# IgnitionSchem.net
KiCad netlist of a schematic drawn in Altium Designer
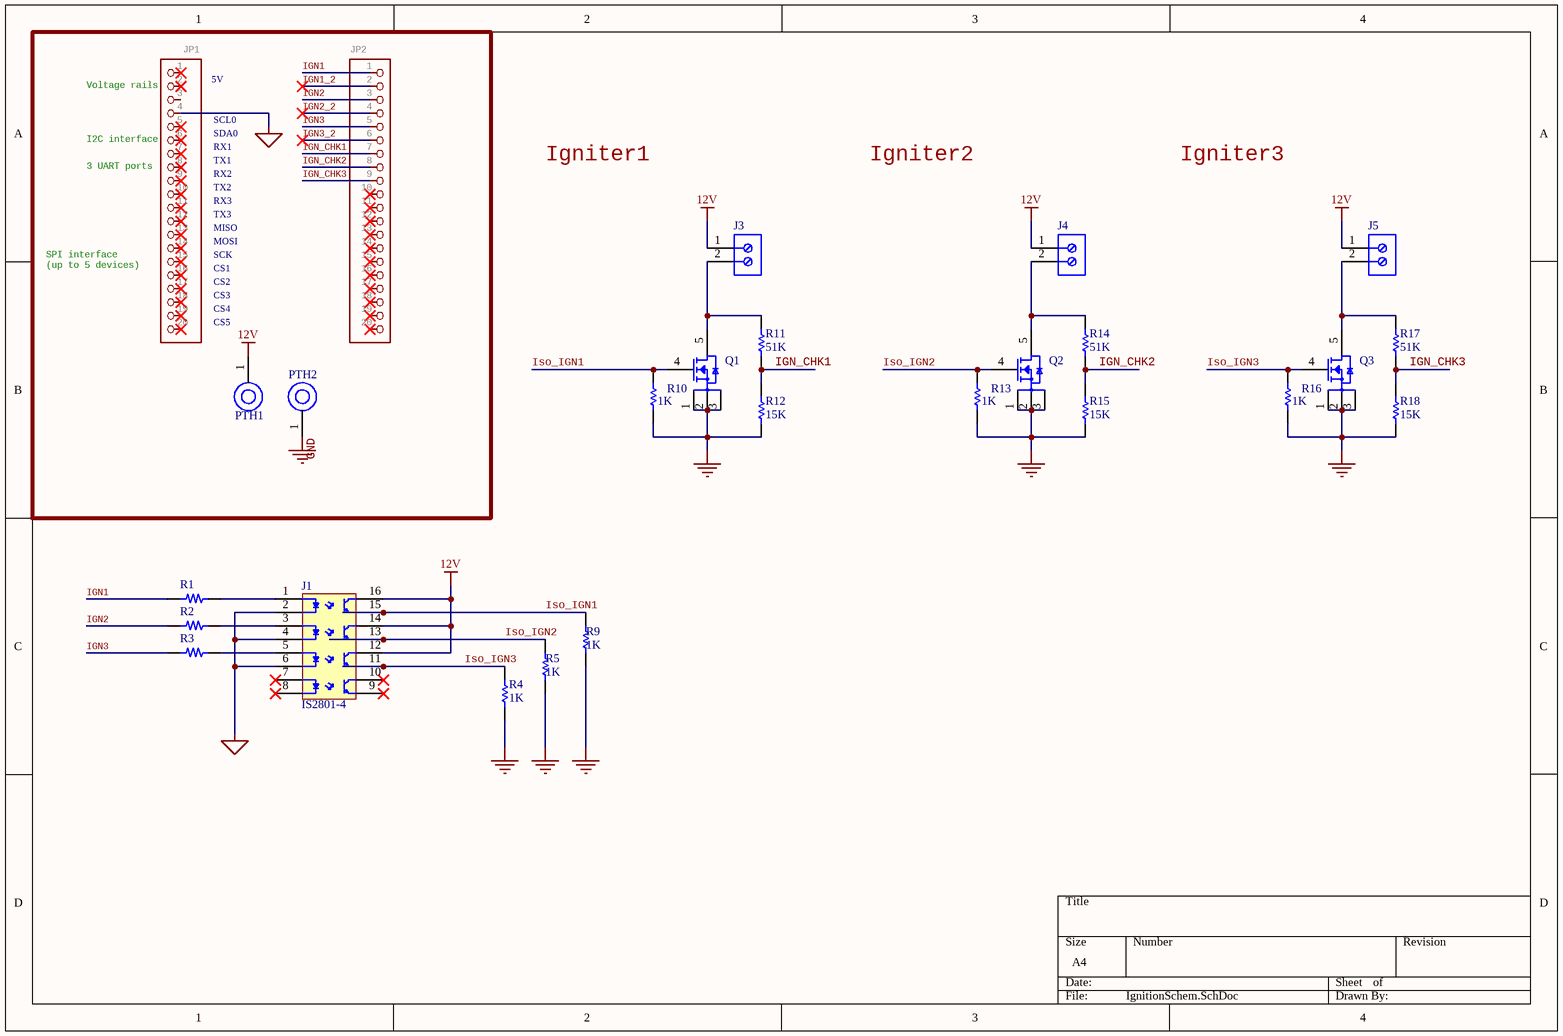
[diagram p0: IgnitionSchem.SchDoc]

(export (version "E")
  (design (tool "Eeschema 10.0.6"))
  (components
    (comp (ref "J1")
      (value "IS2801-4")
      (footprint "SOP127P680X220-16N")
      (description "Optocoupler DC-IN 4-CH Transistor DC-OUT 16-Pin T/R")
      (fields (field (name "MANUFACTURER") "Isocom"))
      (libsource (lib "Avionics_lib") (part "IS2801-4"))
    )
    (comp (ref "J3")
      (value "1725656")
      (footprint "PHOE-1725656-2")
      (description "Male Header, Pitch 2.54 mm, 1 x 2 Position, Height 9 mm, Tail Length 3.5 mm")
      (fields (field (name "MANUFACTURER") "Phoenix Contact"))
      (libsource (lib "Altium Content Vault") (part "CN-1P-F-TB2"))
    )
    (comp (ref "J4")
      (value "1725656")
      (footprint "PHOE-1725656-2")
      (description "Male Header, Pitch 2.54 mm, 1 x 2 Position, Height 9 mm, Tail Length 3.5 mm")
      (fields (field (name "MANUFACTURER") "Phoenix Contact"))
      (libsource (lib "Altium Content Vault") (part "CN-1P-F-TB2"))
    )
    (comp (ref "J5")
      (value "1725656")
      (footprint "PHOE-1725656-2")
      (description "Male Header, Pitch 2.54 mm, 1 x 2 Position, Height 9 mm, Tail Length 3.5 mm")
      (fields (field (name "MANUFACTURER") "Phoenix Contact"))
      (libsource (lib "Altium Content Vault") (part "CN-1P-F-TB2"))
    )
    (comp (ref "JP1")
      (value "PINHD-1X20")
      (footprint "1X20")
      (description "PIN HEADER")
      (libsource (lib "adafruit") (part "PINHD-1X20"))
    )
    (comp (ref "JP2")
      (value "PINHD-1X20")
      (footprint "1X20")
      (description "PIN HEADER")
      (libsource (lib "adafruit") (part "PINHD-1X20"))
    )
    (comp (ref "PTH1")
      (value "WIRE_CONNECTOR")
      (footprint "Wire Mount")
      (libsource (lib "Avionics_lib") (part "WIRE_CONNECTOR"))
    )
    (comp (ref "PTH2")
      (value "WIRE_CONNECTOR")
      (footprint "Wire Mount")
      (libsource (lib "Avionics_lib") (part "WIRE_CONNECTOR"))
    )
    (comp (ref "Q1")
      (value "Ingiter FET")
      (footprint "PSMN5R6-60YLX")
      (description "PSMN5R6-60YL - N-channel 60 V, 5.6 mO logic level MOSFET in LFPAK56")
      (fields
        (field (name "MANUFACTURER") "Nexperia")
        (field (name "MANUFACTURER PART NUMBER") "PSMN5R6-60YLX")
      )
      (libsource (lib "Avionics_lib") (part "PSMN5R6-60YLX"))
    )
    (comp (ref "Q2")
      (value "Ingiter FET")
      (footprint "PSMN5R6-60YLX")
      (description "PSMN5R6-60YL - N-channel 60 V, 5.6 mO logic level MOSFET in LFPAK56")
      (fields
        (field (name "MANUFACTURER") "Nexperia")
        (field (name "MANUFACTURER PART NUMBER") "PSMN5R6-60YLX")
      )
      (libsource (lib "Avionics_lib") (part "PSMN5R6-60YLX"))
    )
    (comp (ref "Q3")
      (value "Ingiter FET")
      (footprint "PSMN5R6-60YLX")
      (description "PSMN5R6-60YL - N-channel 60 V, 5.6 mO logic level MOSFET in LFPAK56")
      (fields
        (field (name "MANUFACTURER") "Nexperia")
        (field (name "MANUFACTURER PART NUMBER") "PSMN5R6-60YLX")
      )
      (libsource (lib "Avionics_lib") (part "PSMN5R6-60YLX"))
    )
    (comp (ref "R1")
      (value "WR06X331JTL")
      (footprint "WR06X331")
      (description "Res Thick Film 0603 330 Ohm 5% 0.1W(1/10W) ±100ppm/C SMD T/R")
      (fields (field (name "MANUFACTURER") "Walsin Technologies") (field (name "TOLERANCE") "5%"))
      (libsource (lib "Avionics_lib") (part "WR06X331JTL"))
    )
    (comp (ref "R2")
      (value "WR06X331JTL")
      (footprint "WR06X331")
      (description "Res Thick Film 0603 330 Ohm 5% 0.1W(1/10W) ±100ppm/C SMD T/R")
      (fields (field (name "MANUFACTURER") "Walsin Technologies") (field (name "TOLERANCE") "5%"))
      (libsource (lib "Avionics_lib") (part "WR06X331JTL"))
    )
    (comp (ref "R3")
      (value "WR06X331JTL")
      (footprint "WR06X331")
      (description "Res Thick Film 0603 330 Ohm 5% 0.1W(1/10W) ±100ppm/C SMD T/R")
      (fields (field (name "MANUFACTURER") "Walsin Technologies") (field (name "TOLERANCE") "5%"))
      (libsource (lib "Avionics_lib") (part "WR06X331JTL"))
    )
    (comp (ref "R4")
      (value "1K")
      (footprint "RESC2013X50X30NL20T20")
      (fields (field (name "PART NUMBER") "CRCW08051K00FKEA") (field (name "MANUFACTURER") "Vishay Dale"))
      (libsource (lib "Altium Content Vault") (part "RES"))
    )
    (comp (ref "R5")
      (value "1K")
      (footprint "RESC2013X50X30NL20T20")
      (fields (field (name "PART NUMBER") "CRCW08051K00FKEA") (field (name "MANUFACTURER") "Vishay Dale"))
      (libsource (lib "Altium Content Vault") (part "RES"))
    )
    (comp (ref "R9")
      (value "1K")
      (footprint "RESC2013X50X30NL20T20")
      (fields (field (name "PART NUMBER") "CRCW08051K00FKEA") (field (name "MANUFACTURER") "Vishay Dale"))
      (libsource (lib "Altium Content Vault") (part "RES"))
    )
    (comp (ref "R10")
      (value "1K")
      (footprint "RESC2013X50X30NL20T20")
      (fields (field (name "PART NUMBER") "CRCW08051K00FKEA") (field (name "MANUFACTURER") "Vishay Dale"))
      (libsource (lib "Altium Content Vault") (part "RES"))
    )
    (comp (ref "R11")
      (value "51K")
      (footprint "RESC2013X60X35NL10T20")
      (fields (field (name "MANUFACTURER") "Yageo") (field (name "PART NUMBER") "RC0805JR-0751KL"))
      (libsource (lib "Altium Content Vault") (part "RES"))
    )
    (comp (ref "R12")
      (value "15K")
      (footprint "RESC0805(2012)_M")
      (description "15K 0.125W 5% 0805 (2012 Metric)  SMD")
      (fields (field (name "POWER") "0.125 W") (field (name "TOLERANCE") "5 %"))
      (libsource (lib "Altium Content Vault") (part "RES"))
    )
    (comp (ref "R13")
      (value "1K")
      (footprint "RESC2013X50X30NL20T20")
      (fields (field (name "PART NUMBER") "CRCW08051K00FKEA") (field (name "MANUFACTURER") "Vishay Dale"))
      (libsource (lib "Altium Content Vault") (part "RES"))
    )
    (comp (ref "R14")
      (value "51K")
      (footprint "RESC2013X60X35NL10T20")
      (fields (field (name "MANUFACTURER") "Yageo") (field (name "PART NUMBER") "RC0805JR-0751KL"))
      (libsource (lib "Altium Content Vault") (part "RES"))
    )
    (comp (ref "R15")
      (value "15K")
      (footprint "RESC0805(2012)_M")
      (description "15K 0.125W 5% 0805 (2012 Metric)  SMD")
      (fields (field (name "POWER") "0.125 W") (field (name "TOLERANCE") "5 %"))
      (libsource (lib "Altium Content Vault") (part "RES"))
    )
    (comp (ref "R16")
      (value "1K")
      (footprint "RESC2013X50X30NL20T20")
      (fields (field (name "PART NUMBER") "CRCW08051K00FKEA") (field (name "MANUFACTURER") "Vishay Dale"))
      (libsource (lib "Altium Content Vault") (part "RES"))
    )
    (comp (ref "R17")
      (value "51K")
      (footprint "RESC2013X60X35NL10T20")
      (fields (field (name "MANUFACTURER") "Yageo") (field (name "PART NUMBER") "RC0805JR-0751KL"))
      (libsource (lib "Altium Content Vault") (part "RES"))
    )
    (comp (ref "R18")
      (value "15K")
      (footprint "RESC0805(2012)_M")
      (description "15K 0.125W 5% 0805 (2012 Metric)  SMD")
      (fields (field (name "POWER") "0.125 W") (field (name "TOLERANCE") "5 %"))
      (libsource (lib "Altium Content Vault") (part "RES"))
    )
  )
  (nets
    (net (code "1") (name "/IGN1") (class "Default")
      (node (ref "JP2") (pin "1") (pinfunction "1_1") (pintype "passive"))
      (node (ref "R1") (pin "1") (pinfunction "1_1") (pintype "passive"))
    )
    (net (code "2") (name "/IGN1_2") (class "Default")
      (node (ref "JP2") (pin "2") (pinfunction "2_2") (pintype "passive+no_connect"))
    )
    (net (code "3") (name "/IGN2") (class "Default")
      (node (ref "JP2") (pin "3") (pinfunction "3_3") (pintype "passive"))
      (node (ref "R2") (pin "1") (pinfunction "1_1") (pintype "passive"))
    )
    (net (code "4") (name "/IGN2_2") (class "Default")
      (node (ref "JP2") (pin "4") (pinfunction "4_4") (pintype "passive+no_connect"))
    )
    (net (code "5") (name "/IGN3") (class "Default")
      (node (ref "JP2") (pin "5") (pinfunction "5_5") (pintype "passive"))
      (node (ref "R3") (pin "1") (pinfunction "1_1") (pintype "passive"))
    )
    (net (code "6") (name "/IGN3_2") (class "Default")
      (node (ref "JP2") (pin "6") (pinfunction "6_6") (pintype "passive+no_connect"))
    )
    (net (code "7") (name "/IGN_CHK1") (class "Default")
      (node (ref "JP2") (pin "7") (pinfunction "7_7") (pintype "passive"))
      (node (ref "R11") (pin "1") (pinfunction "1_1") (pintype "passive"))
      (node (ref "R12") (pin "2") (pinfunction "2_2") (pintype "passive"))
    )
    (net (code "8") (name "/IGN_CHK2") (class "Default")
      (node (ref "JP2") (pin "8") (pinfunction "8_8") (pintype "passive"))
      (node (ref "R14") (pin "1") (pinfunction "1_1") (pintype "passive"))
      (node (ref "R15") (pin "2") (pinfunction "2_2") (pintype "passive"))
    )
    (net (code "9") (name "/IGN_CHK3") (class "Default")
      (node (ref "JP2") (pin "9") (pinfunction "9_9") (pintype "passive"))
      (node (ref "R17") (pin "1") (pinfunction "1_1") (pintype "passive"))
      (node (ref "R18") (pin "2") (pinfunction "2_2") (pintype "passive"))
    )
    (net (code "10") (name "/Iso_IGN1") (class "Default")
      (node (ref "J1") (pin "15") (pinfunction "15_15") (pintype "passive"))
      (node (ref "Q1") (pin "4") (pinfunction "4_4") (pintype "passive"))
      (node (ref "R10") (pin "2") (pinfunction "2_2") (pintype "passive"))
      (node (ref "R9") (pin "2") (pinfunction "2_2") (pintype "passive"))
    )
    (net (code "11") (name "/Iso_IGN2") (class "Default")
      (node (ref "J1") (pin "13") (pinfunction "13_13") (pintype "passive"))
      (node (ref "Q2") (pin "4") (pinfunction "4_4") (pintype "passive"))
      (node (ref "R13") (pin "2") (pinfunction "2_2") (pintype "passive"))
      (node (ref "R5") (pin "2") (pinfunction "2_2") (pintype "passive"))
    )
    (net (code "12") (name "/Iso_IGN3") (class "Default")
      (node (ref "J1") (pin "11") (pinfunction "11_11") (pintype "passive"))
      (node (ref "Q3") (pin "4") (pinfunction "4_4") (pintype "passive"))
      (node (ref "R16") (pin "2") (pinfunction "2_2") (pintype "passive"))
      (node (ref "R4") (pin "2") (pinfunction "2_2") (pintype "passive"))
    )
    (net (code "13") (name "12V") (class "Default")
      (node (ref "J1") (pin "12") (pinfunction "12_12") (pintype "passive"))
      (node (ref "J1") (pin "14") (pinfunction "14_14") (pintype "passive"))
      (node (ref "J1") (pin "16") (pinfunction "16_16") (pintype "passive"))
      (node (ref "J3") (pin "1") (pinfunction "1_1") (pintype "passive"))
      (node (ref "J4") (pin "1") (pinfunction "1_1") (pintype "passive"))
      (node (ref "J5") (pin "1") (pinfunction "1_1") (pintype "passive"))
      (node (ref "PTH1") (pin "1") (pinfunction "1_1") (pintype "passive"))
    )
    (net (code "14") (name "GND") (class "Default")
      (node (ref "PTH2") (pin "1") (pinfunction "1_1") (pintype "passive"))
      (node (ref "Q1") (pin "1") (pinfunction "1_1") (pintype "passive"))
      (node (ref "Q1") (pin "2") (pinfunction "2_2") (pintype "passive"))
      (node (ref "Q1") (pin "3") (pinfunction "3_3") (pintype "passive"))
      (node (ref "Q2") (pin "1") (pinfunction "1_1") (pintype "passive"))
      (node (ref "Q2") (pin "2") (pinfunction "2_2") (pintype "passive"))
      (node (ref "Q2") (pin "3") (pinfunction "3_3") (pintype "passive"))
      (node (ref "Q3") (pin "1") (pinfunction "1_1") (pintype "passive"))
      (node (ref "Q3") (pin "2") (pinfunction "2_2") (pintype "passive"))
      (node (ref "Q3") (pin "3") (pinfunction "3_3") (pintype "passive"))
      (node (ref "R10") (pin "1") (pinfunction "1_1") (pintype "passive"))
      (node (ref "R12") (pin "1") (pinfunction "1_1") (pintype "passive"))
      (node (ref "R13") (pin "1") (pinfunction "1_1") (pintype "passive"))
      (node (ref "R15") (pin "1") (pinfunction "1_1") (pintype "passive"))
      (node (ref "R16") (pin "1") (pinfunction "1_1") (pintype "passive"))
      (node (ref "R18") (pin "1") (pinfunction "1_1") (pintype "passive"))
      (node (ref "R4") (pin "1") (pinfunction "1_1") (pintype "passive"))
      (node (ref "R5") (pin "1") (pinfunction "1_1") (pintype "passive"))
      (node (ref "R9") (pin "1") (pinfunction "1_1") (pintype "passive"))
    )
    (net (code "15") (name "MCU_GND") (class "Default")
      (node (ref "J1") (pin "2") (pinfunction "2_2") (pintype "passive"))
      (node (ref "J1") (pin "4") (pinfunction "4_4") (pintype "passive"))
      (node (ref "J1") (pin "6") (pinfunction "6_6") (pintype "passive"))
      (node (ref "JP1") (pin "4") (pinfunction "4_4") (pintype "passive"))
    )
    (net (code "16") (name "Net-(J1-Pad1)") (class "Default")
      (node (ref "J1") (pin "1") (pinfunction "1_1") (pintype "passive"))
      (node (ref "R1") (pin "2") (pinfunction "2_2") (pintype "passive"))
    )
    (net (code "17") (name "Net-(J1-Pad3)") (class "Default")
      (node (ref "J1") (pin "3") (pinfunction "3_3") (pintype "passive"))
      (node (ref "R2") (pin "2") (pinfunction "2_2") (pintype "passive"))
    )
    (net (code "18") (name "Net-(J1-Pad5)") (class "Default")
      (node (ref "J1") (pin "5") (pinfunction "5_5") (pintype "passive"))
      (node (ref "R3") (pin "2") (pinfunction "2_2") (pintype "passive"))
    )
    (net (code "19") (name "Net-(J3-Pad2)") (class "Default")
      (node (ref "J3") (pin "2") (pinfunction "2_2") (pintype "passive"))
      (node (ref "Q1") (pin "5") (pinfunction "5_5") (pintype "passive"))
      (node (ref "R11") (pin "2") (pinfunction "2_2") (pintype "passive"))
    )
    (net (code "20") (name "Net-(J4-Pad2)") (class "Default")
      (node (ref "J4") (pin "2") (pinfunction "2_2") (pintype "passive"))
      (node (ref "Q2") (pin "5") (pinfunction "5_5") (pintype "passive"))
      (node (ref "R14") (pin "2") (pinfunction "2_2") (pintype "passive"))
    )
    (net (code "21") (name "Net-(J5-Pad2)") (class "Default")
      (node (ref "J5") (pin "2") (pinfunction "2_2") (pintype "passive"))
      (node (ref "Q3") (pin "5") (pinfunction "5_5") (pintype "passive"))
      (node (ref "R17") (pin "2") (pinfunction "2_2") (pintype "passive"))
    )
    (net (code "22") (name "unconnected-(J1-Pad7)") (class "Default")
      (node (ref "J1") (pin "7") (pinfunction "7_7") (pintype "passive+no_connect"))
    )
    (net (code "23") (name "unconnected-(J1-Pad8)") (class "Default")
      (node (ref "J1") (pin "8") (pinfunction "8_8") (pintype "passive+no_connect"))
    )
    (net (code "24") (name "unconnected-(J1-Pad9)") (class "Default")
      (node (ref "J1") (pin "9") (pinfunction "9_9") (pintype "passive+no_connect"))
    )
    (net (code "25") (name "unconnected-(J1-Pad10)") (class "Default")
      (node (ref "J1") (pin "10") (pinfunction "10_10") (pintype "passive+no_connect"))
    )
    (net (code "26") (name "unconnected-(JP1-Pad1)") (class "Default")
      (node (ref "JP1") (pin "1") (pinfunction "1_1") (pintype "passive+no_connect"))
    )
    (net (code "27") (name "unconnected-(JP1-Pad2)") (class "Default")
      (node (ref "JP1") (pin "2") (pinfunction "2_2") (pintype "passive+no_connect"))
    )
    (net (code "28") (name "unconnected-(JP1-Pad3)") (class "Default")
      (node (ref "JP1") (pin "3") (pinfunction "3_3") (pintype "passive"))
    )
    (net (code "29") (name "unconnected-(JP1-Pad5)") (class "Default")
      (node (ref "JP1") (pin "5") (pinfunction "5_5") (pintype "passive+no_connect"))
    )
    (net (code "30") (name "unconnected-(JP1-Pad6)") (class "Default")
      (node (ref "JP1") (pin "6") (pinfunction "6_6") (pintype "passive+no_connect"))
    )
    (net (code "31") (name "unconnected-(JP1-Pad7)") (class "Default")
      (node (ref "JP1") (pin "7") (pinfunction "7_7") (pintype "passive+no_connect"))
    )
    (net (code "32") (name "unconnected-(JP1-Pad8)") (class "Default")
      (node (ref "JP1") (pin "8") (pinfunction "8_8") (pintype "passive+no_connect"))
    )
    (net (code "33") (name "unconnected-(JP1-Pad9)") (class "Default")
      (node (ref "JP1") (pin "9") (pinfunction "9_9") (pintype "passive+no_connect"))
    )
    (net (code "34") (name "unconnected-(JP1-Pad10)") (class "Default")
      (node (ref "JP1") (pin "10") (pinfunction "10_10") (pintype "passive+no_connect"))
    )
    (net (code "35") (name "unconnected-(JP1-Pad11)") (class "Default")
      (node (ref "JP1") (pin "11") (pinfunction "11_11") (pintype "passive+no_connect"))
    )
    (net (code "36") (name "unconnected-(JP1-Pad12)") (class "Default")
      (node (ref "JP1") (pin "12") (pinfunction "12_12") (pintype "passive+no_connect"))
    )
    (net (code "37") (name "unconnected-(JP1-Pad13)") (class "Default")
      (node (ref "JP1") (pin "13") (pinfunction "13_13") (pintype "passive+no_connect"))
    )
    (net (code "38") (name "unconnected-(JP1-Pad14)") (class "Default")
      (node (ref "JP1") (pin "14") (pinfunction "14_14") (pintype "passive+no_connect"))
    )
    (net (code "39") (name "unconnected-(JP1-Pad15)") (class "Default")
      (node (ref "JP1") (pin "15") (pinfunction "15_15") (pintype "passive+no_connect"))
    )
    (net (code "40") (name "unconnected-(JP1-Pad16)") (class "Default")
      (node (ref "JP1") (pin "16") (pinfunction "16_16") (pintype "passive+no_connect"))
    )
    (net (code "41") (name "unconnected-(JP1-Pad17)") (class "Default")
      (node (ref "JP1") (pin "17") (pinfunction "17_17") (pintype "passive+no_connect"))
    )
    (net (code "42") (name "unconnected-(JP1-Pad18)") (class "Default")
      (node (ref "JP1") (pin "18") (pinfunction "18_18") (pintype "passive+no_connect"))
    )
    (net (code "43") (name "unconnected-(JP1-Pad19)") (class "Default")
      (node (ref "JP1") (pin "19") (pinfunction "19_19") (pintype "passive+no_connect"))
    )
    (net (code "44") (name "unconnected-(JP1-Pad20)") (class "Default")
      (node (ref "JP1") (pin "20") (pinfunction "20_20") (pintype "passive+no_connect"))
    )
    (net (code "45") (name "unconnected-(JP2-Pad10)") (class "Default")
      (node (ref "JP2") (pin "10") (pinfunction "10_10") (pintype "passive+no_connect"))
    )
    (net (code "46") (name "unconnected-(JP2-Pad11)") (class "Default")
      (node (ref "JP2") (pin "11") (pinfunction "11_11") (pintype "passive+no_connect"))
    )
    (net (code "47") (name "unconnected-(JP2-Pad12)") (class "Default")
      (node (ref "JP2") (pin "12") (pinfunction "12_12") (pintype "passive+no_connect"))
    )
    (net (code "48") (name "unconnected-(JP2-Pad13)") (class "Default")
      (node (ref "JP2") (pin "13") (pinfunction "13_13") (pintype "passive+no_connect"))
    )
    (net (code "49") (name "unconnected-(JP2-Pad14)") (class "Default")
      (node (ref "JP2") (pin "14") (pinfunction "14_14") (pintype "passive+no_connect"))
    )
    (net (code "50") (name "unconnected-(JP2-Pad15)") (class "Default")
      (node (ref "JP2") (pin "15") (pinfunction "15_15") (pintype "passive+no_connect"))
    )
    (net (code "51") (name "unconnected-(JP2-Pad16)") (class "Default")
      (node (ref "JP2") (pin "16") (pinfunction "16_16") (pintype "passive+no_connect"))
    )
    (net (code "52") (name "unconnected-(JP2-Pad17)") (class "Default")
      (node (ref "JP2") (pin "17") (pinfunction "17_17") (pintype "passive+no_connect"))
    )
    (net (code "53") (name "unconnected-(JP2-Pad18)") (class "Default")
      (node (ref "JP2") (pin "18") (pinfunction "18_18") (pintype "passive+no_connect"))
    )
    (net (code "54") (name "unconnected-(JP2-Pad19)") (class "Default")
      (node (ref "JP2") (pin "19") (pinfunction "19_19") (pintype "passive+no_connect"))
    )
    (net (code "55") (name "unconnected-(JP2-Pad20)") (class "Default")
      (node (ref "JP2") (pin "20") (pinfunction "20_20") (pintype "passive+no_connect"))
    )
  )
)
